# NCP718_Breakout.net
KiCad netlist of a schematic drawn in Altium Designer
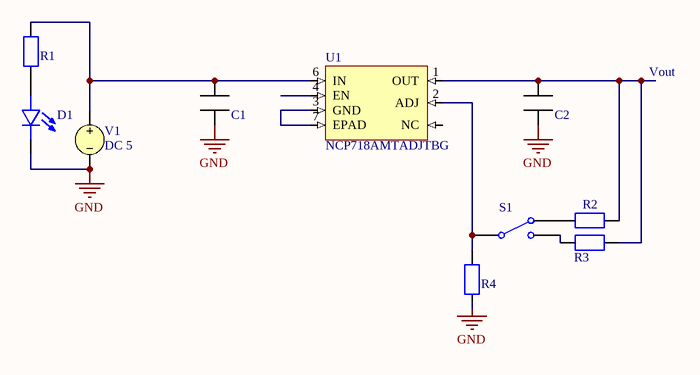
[diagram p0: NCP718_Breakout.SchDoc]

(export (version "E")
  (design (tool "Eeschema 10.0.6"))
  (components
    (comp (ref "C1")
      (value "CAP_0805")
      (footprint "RES_0805")
      (description "Generic CAP_0805")
      (libsource (lib "Integrated_Library1") (part "CAP_0805"))
    )
    (comp (ref "C2")
      (value "CAP_0805")
      (footprint "RES_0805")
      (description "Generic CAP_0805")
      (libsource (lib "Integrated_Library1") (part "CAP_0805"))
    )
    (comp (ref "D1")
      (value "LED_0805")
      (footprint "RES_0805")
      (description "LED; SMD;")
      (fields (field (name "MF") "Kingbright") (field (name "MP") "KP-1608SURCK"))
      (libsource (lib "Integrated_Library1") (part "LED_0805"))
    )
    (comp (ref "R1")
      (value "RES_0805")
      (footprint "RES_0805")
      (description "Resistor SMD 0805 Generic")
      (libsource (lib "Integrated_Library1") (part "RES_0805"))
    )
    (comp (ref "R2")
      (value "RES_0805")
      (footprint "RES_0805")
      (description "Resistor SMD 0805 Generic")
      (libsource (lib "Integrated_Library1") (part "RES_0805"))
    )
    (comp (ref "R3")
      (value "RES_0805")
      (footprint "RES_0805")
      (description "Resistor SMD 0805 Generic")
      (libsource (lib "Integrated_Library1") (part "RES_0805"))
    )
    (comp (ref "R4")
      (value "RES_0805")
      (footprint "RES_0805")
      (description "Resistor SMD 0805 Generic")
      (libsource (lib "Integrated_Library1") (part "RES_0805"))
    )
    (comp (ref "S1")
      (value "Single-Pole, Double-Throw Switch")
      (libsource (lib "Simulation Generic Components") (part "SPDT SW"))
    )
    (comp (ref "U1")
      (value "NCP718AMTADJTBG")
      (footprint "FP-511BR-MFG")
      (description "LDO Regulator, 300 mA, Wide Vin, Ultra-Low Iq Adjustable, Active Discharge, WDFN6")
      (fields (field (name "MANUFACTURER") "onsemi"))
      (libsource (lib "Integrated_Library1") (part "NCP718AMTADJTBG"))
    )
    (comp (ref "V1")
      (value "DC 5")
      (description "Voltage Source")
      (fields (field (name "PUBLISHER") "Altium Limited"))
      (libsource (lib "Simulation Generic Components") (part "VSRC"))
    )
  )
  (nets
    (net (code "1") (name "GND") (class "Default")
      (node (ref "C1") (pin "6") (pinfunction "6_6") (pintype "passive"))
      (node (ref "C2") (pin "6") (pinfunction "6_6") (pintype "passive"))
      (node (ref "D1") (pin "2") (pinfunction "C_2") (pintype "passive"))
      (node (ref "R4") (pin "1") (pintype "passive"))
      (node (ref "V1") (pin "2") (pinfunction "2_2") (pintype "passive"))
    )
    (net (code "2") (name "Net-(D1-A)") (class "Default")
      (node (ref "D1") (pin "1") (pinfunction "A_1") (pintype "passive"))
      (node (ref "R1") (pin "2") (pintype "passive"))
    )
    (net (code "3") (name "Net-(R2-Pad1)") (class "Default")
      (node (ref "R2") (pin "1") (pintype "passive"))
      (node (ref "S1") (pin "3") (pinfunction "3_3") (pintype "passive"))
    )
    (net (code "4") (name "Net-(R3-Pad1)") (class "Default")
      (node (ref "R3") (pin "1") (pintype "passive"))
      (node (ref "S1") (pin "2") (pinfunction "2_2") (pintype "passive"))
    )
    (net (code "5") (name "Net-(U1-ADJ)") (class "Default")
      (node (ref "R4") (pin "2") (pintype "passive"))
      (node (ref "S1") (pin "1") (pinfunction "1_1") (pintype "passive"))
      (node (ref "U1") (pin "2") (pinfunction "ADJ_2") (pintype "input"))
    )
    (net (code "6") (name "Net-(U1-EPAD)") (class "Default")
      (node (ref "U1") (pin "3") (pinfunction "GND_3") (pintype "input"))
      (node (ref "U1") (pin "7") (pinfunction "EPAD_7") (pintype "input"))
    )
    (net (code "7") (name "Net-(U1-IN)") (class "Default")
      (node (ref "C1") (pin "7") (pinfunction "7_7") (pintype "passive"))
      (node (ref "R1") (pin "1") (pintype "passive"))
      (node (ref "U1") (pin "6") (pinfunction "IN_6") (pintype "input"))
      (node (ref "V1") (pin "1") (pinfunction "1_1") (pintype "passive"))
    )
    (net (code "8") (name "Net-(U1-OUT)") (class "Default")
      (node (ref "C2") (pin "7") (pinfunction "7_7") (pintype "passive"))
      (node (ref "R2") (pin "2") (pintype "passive"))
      (node (ref "R3") (pin "2") (pintype "passive"))
      (node (ref "U1") (pin "1") (pinfunction "OUT_1") (pintype "input"))
    )
    (net (code "9") (name "unconnected-(U1-EN-Pad4)") (class "Default")
      (node (ref "U1") (pin "4") (pinfunction "EN_4") (pintype "input"))
    )
    (net (code "10") (name "unconnected-(U1-NC-Pad5)") (class "Default")
      (node (ref "U1") (pin "5") (pinfunction "NC_5") (pintype "input"))
    )
  )
)
